# motor_controllers_connection.net
KiCad netlist of a schematic drawn in Altium Designer
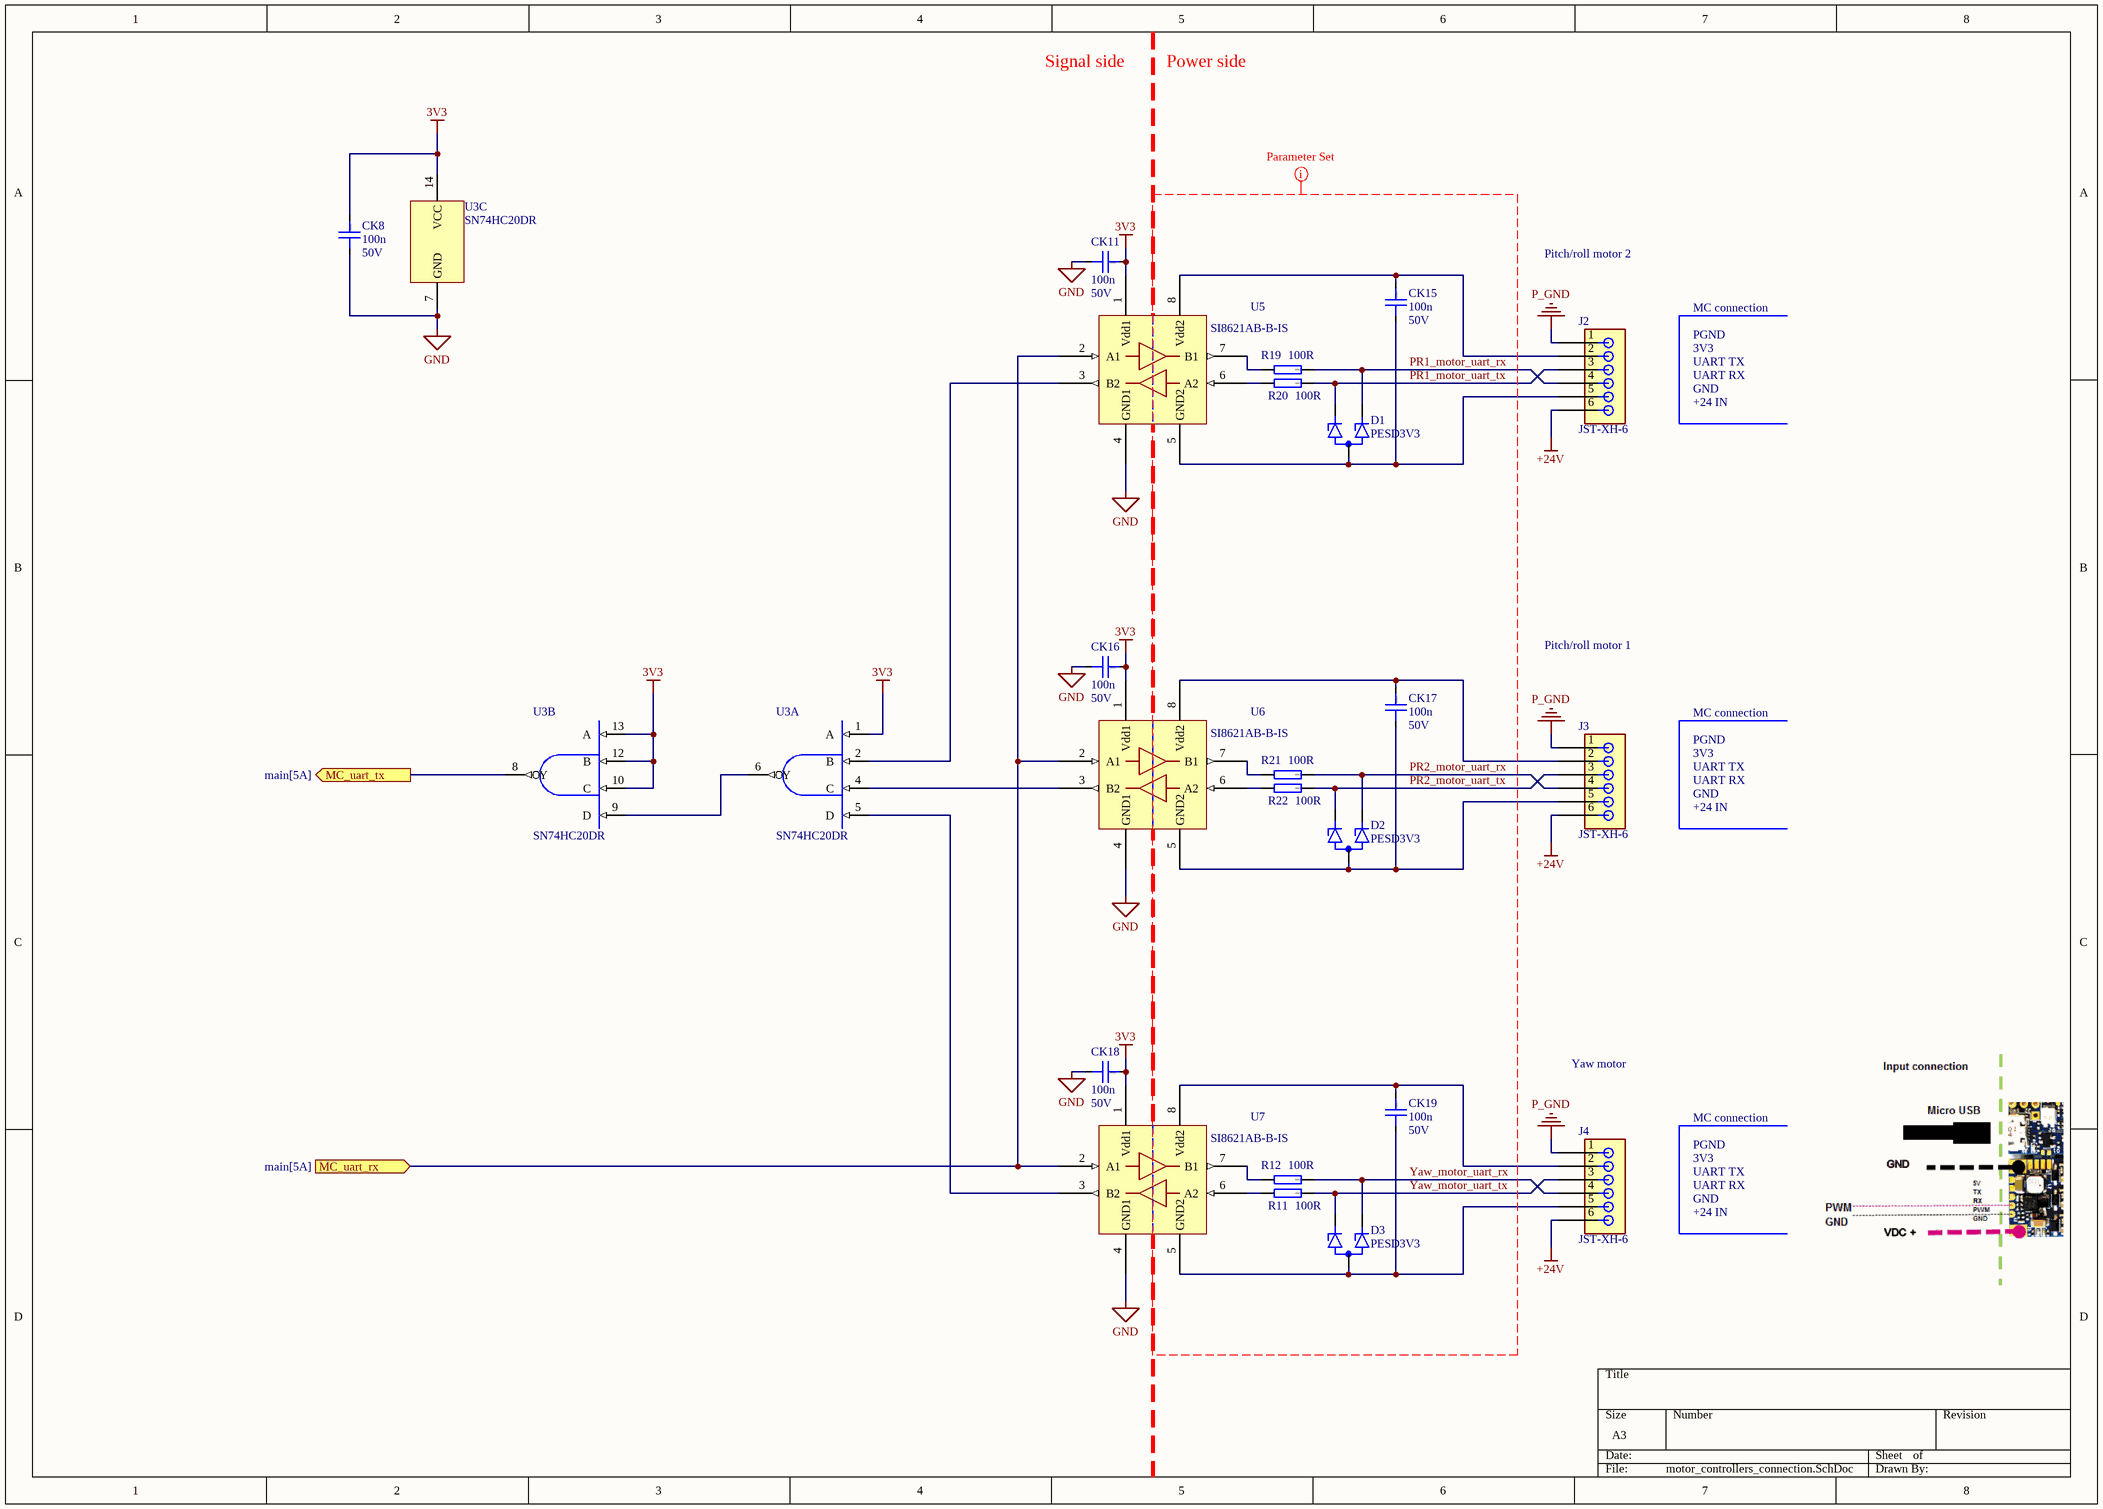
[diagram p0: motor_controllers_connection.SchDoc]

(export (version "E")
  (design (tool "Eeschema 10.0.6"))
  (components
    (comp (ref "CK8")
      (value "100n")
      (footprint "CAP0603")
      (description "50V 100nF X7R ±10% 0603 Multilayer Ceramic Capacitors MLCC - SMD/SMT ROHS")
      (fields (field (name "JLCPCB PART") "C14663") (field (name "VOLTAGE RATING") "50V"))
      (libsource (lib "Kubikova ultra knihovna") (part "Cap 100n 0603"))
    )
    (comp (ref "CK11")
      (value "100n")
      (footprint "CAP0603")
      (description "50V 100nF X7R ±10% 0603 Multilayer Ceramic Capacitors MLCC - SMD/SMT ROHS")
      (fields (field (name "JLCPCB PART") "C14663") (field (name "VOLTAGE RATING") "50V"))
      (libsource (lib "Kubikova ultra knihovna") (part "Cap 100n 0603"))
    )
    (comp (ref "CK15")
      (value "100n")
      (footprint "CAP0603")
      (description "50V 100nF X7R ±10% 0603 Multilayer Ceramic Capacitors MLCC - SMD/SMT ROHS")
      (fields (field (name "JLCPCB PART") "C14663") (field (name "VOLTAGE RATING") "50V"))
      (libsource (lib "Kubikova ultra knihovna") (part "Cap 100n 0603"))
    )
    (comp (ref "CK16")
      (value "100n")
      (footprint "CAP0603")
      (description "50V 100nF X7R ±10% 0603 Multilayer Ceramic Capacitors MLCC - SMD/SMT ROHS")
      (fields (field (name "JLCPCB PART") "C14663") (field (name "VOLTAGE RATING") "50V"))
      (libsource (lib "Kubikova ultra knihovna") (part "Cap 100n 0603"))
    )
    (comp (ref "CK17")
      (value "100n")
      (footprint "CAP0603")
      (description "50V 100nF X7R ±10% 0603 Multilayer Ceramic Capacitors MLCC - SMD/SMT ROHS")
      (fields (field (name "JLCPCB PART") "C14663") (field (name "VOLTAGE RATING") "50V"))
      (libsource (lib "Kubikova ultra knihovna") (part "Cap 100n 0603"))
    )
    (comp (ref "CK18")
      (value "100n")
      (footprint "CAP0603")
      (description "50V 100nF X7R ±10% 0603 Multilayer Ceramic Capacitors MLCC - SMD/SMT ROHS")
      (fields (field (name "JLCPCB PART") "C14663") (field (name "VOLTAGE RATING") "50V"))
      (libsource (lib "Kubikova ultra knihovna") (part "Cap 100n 0603"))
    )
    (comp (ref "CK19")
      (value "100n")
      (footprint "CAP0603")
      (description "50V 100nF X7R ±10% 0603 Multilayer Ceramic Capacitors MLCC - SMD/SMT ROHS")
      (fields (field (name "JLCPCB PART") "C14663") (field (name "VOLTAGE RATING") "50V"))
      (libsource (lib "Kubikova ultra knihovna") (part "Cap 100n 0603"))
    )
    (comp (ref "D1")
      (value "PESD3V3")
      (footprint "SOT95P230X110-3N(SOT23)")
      (description "18A 20V 5.2V Unidirectional 3.3V SOT-23 ESD and Surge Protection (TVS/ESD) ROHS")
      (fields (field (name "JLCPCB PART") "C84276") (field (name "TME PART") "PESD3V3S2UT.215"))
      (libsource (lib "Kubikova ultra knihovna") (part "PESD3V3S2UT,215"))
    )
    (comp (ref "D2")
      (value "PESD3V3")
      (footprint "SOT95P230X110-3N(SOT23)")
      (description "18A 20V 5.2V Unidirectional 3.3V SOT-23 ESD and Surge Protection (TVS/ESD) ROHS")
      (fields (field (name "JLCPCB PART") "C84276") (field (name "TME PART") "PESD3V3S2UT.215"))
      (libsource (lib "Kubikova ultra knihovna") (part "PESD3V3S2UT,215"))
    )
    (comp (ref "D3")
      (value "PESD3V3")
      (footprint "SOT95P230X110-3N(SOT23)")
      (description "18A 20V 5.2V Unidirectional 3.3V SOT-23 ESD and Surge Protection (TVS/ESD) ROHS")
      (fields (field (name "JLCPCB PART") "C84276") (field (name "TME PART") "PESD3V3S2UT.215"))
      (libsource (lib "Kubikova ultra knihovna") (part "PESD3V3S2UT,215"))
    )
    (comp (ref "J2")
      (value "JST-XH-6")
      (footprint "JST-XH-6")
      (fields (field (name "JLCPCB PART") "C157919") (field (name "TME PART") "S6B-XH-A"))
      (libsource (lib "Kubikova ultra knihovna") (part "JST-HX-6"))
    )
    (comp (ref "J3")
      (value "JST-XH-6")
      (footprint "JST-XH-6")
      (fields (field (name "JLCPCB PART") "C157919") (field (name "TME PART") "S6B-XH-A"))
      (libsource (lib "Kubikova ultra knihovna") (part "JST-HX-6"))
    )
    (comp (ref "J4")
      (value "JST-XH-6")
      (footprint "JST-XH-6")
      (fields (field (name "JLCPCB PART") "C157919") (field (name "TME PART") "S6B-XH-A"))
      (libsource (lib "Kubikova ultra knihovna") (part "JST-HX-6"))
    )
    (comp (ref "R11")
      (value "100R")
      (footprint "RESC2012X06N(SMR0805)")
      (description "125mW Thick Film Resistors 150V ±100ppm/℃ ±1% 100Ω 0805 Chip Resistor - Surface Mount ROHS")
      (fields (field (name "JLCPCB PART") "C17408") (field (name "AUTHOR") "JP/27.03.2014"))
      (libsource (lib "Kubikova ultra knihovna") (part "Res 100R 0805"))
    )
    (comp (ref "R12")
      (value "100R")
      (footprint "RESC2012X06N(SMR0805)")
      (description "125mW Thick Film Resistors 150V ±100ppm/℃ ±1% 100Ω 0805 Chip Resistor - Surface Mount ROHS")
      (fields (field (name "JLCPCB PART") "C17408") (field (name "AUTHOR") "JP/27.03.2014"))
      (libsource (lib "Kubikova ultra knihovna") (part "Res 100R 0805"))
    )
    (comp (ref "R19")
      (value "100R")
      (footprint "RESC2012X06N(SMR0805)")
      (description "125mW Thick Film Resistors 150V ±100ppm/℃ ±1% 100Ω 0805 Chip Resistor - Surface Mount ROHS")
      (fields (field (name "JLCPCB PART") "C17408") (field (name "AUTHOR") "JP/27.03.2014"))
      (libsource (lib "Kubikova ultra knihovna") (part "Res 100R 0805"))
    )
    (comp (ref "R20")
      (value "100R")
      (footprint "RESC2012X06N(SMR0805)")
      (description "125mW Thick Film Resistors 150V ±100ppm/℃ ±1% 100Ω 0805 Chip Resistor - Surface Mount ROHS")
      (fields (field (name "JLCPCB PART") "C17408") (field (name "AUTHOR") "JP/27.03.2014"))
      (libsource (lib "Kubikova ultra knihovna") (part "Res 100R 0805"))
    )
    (comp (ref "R21")
      (value "100R")
      (footprint "RESC2012X06N(SMR0805)")
      (description "125mW Thick Film Resistors 150V ±100ppm/℃ ±1% 100Ω 0805 Chip Resistor - Surface Mount ROHS")
      (fields (field (name "JLCPCB PART") "C17408") (field (name "AUTHOR") "JP/27.03.2014"))
      (libsource (lib "Kubikova ultra knihovna") (part "Res 100R 0805"))
    )
    (comp (ref "R22")
      (value "100R")
      (footprint "RESC2012X06N(SMR0805)")
      (description "125mW Thick Film Resistors 150V ±100ppm/℃ ±1% 100Ω 0805 Chip Resistor - Surface Mount ROHS")
      (fields (field (name "JLCPCB PART") "C17408") (field (name "AUTHOR") "JP/27.03.2014"))
      (libsource (lib "Kubikova ultra knihovna") (part "Res 100R 0805"))
    )
    (comp (ref "U3")
      (value "SN74HC20DR")
      (footprint "SOIC14")
      (description "2V~6V 2uA 2 19ns@6V,50pF NAND Gates SOIC-14 Logic Gates ROHS")
      (fields (field (name "JLCPCB PART") "C2867684"))
      (libsource (lib "Kubikova ultra knihovna") (part "SN74HC20DR"))
    )
    (comp (ref "U5")
      (value "SI8621AB-B-IS")
      (footprint "SOIC8")
      (description "SOIC-8 Digital Isolators ROHS")
      (fields (field (name "JLCPCB PART") "C430265"))
      (libsource (lib "Kubikova ultra knihovna") (part "SI8621AB-B-IS"))
    )
    (comp (ref "U6")
      (value "SI8621AB-B-IS")
      (footprint "SOIC8")
      (description "SOIC-8 Digital Isolators ROHS")
      (fields (field (name "JLCPCB PART") "C430265"))
      (libsource (lib "Kubikova ultra knihovna") (part "SI8621AB-B-IS"))
    )
    (comp (ref "U7")
      (value "SI8621AB-B-IS")
      (footprint "SOIC8")
      (description "SOIC-8 Digital Isolators ROHS")
      (fields (field (name "JLCPCB PART") "C430265"))
      (libsource (lib "Kubikova ultra knihovna") (part "SI8621AB-B-IS"))
    )
  )
  (nets
    (net (code "1") (name "+24V") (class "Default")
      (node (ref "J2") (pin "6") (pinfunction "6_6") (pintype "passive"))
      (node (ref "J3") (pin "6") (pinfunction "6_6") (pintype "passive"))
      (node (ref "J4") (pin "6") (pinfunction "6_6") (pintype "passive"))
    )
    (net (code "2") (name "/MC_uart_rx") (class "Default")
      (node (ref "U5") (pin "2") (pinfunction "A1_2") (pintype "input"))
      (node (ref "U6") (pin "2") (pinfunction "A1_2") (pintype "input"))
      (node (ref "U7") (pin "2") (pinfunction "A1_2") (pintype "input"))
    )
    (net (code "3") (name "/MC_uart_tx") (class "Default")
      (node (ref "U3") (pin "8") (pinfunction "Y_8") (pintype "output"))
    )
    (net (code "4") (name "/PR1_motor_uart_rx") (class "Default")
      (node (ref "D1") (pin "1") (pinfunction "K1_1") (pintype "passive"))
      (node (ref "J2") (pin "4") (pinfunction "4_4") (pintype "passive"))
      (node (ref "R19") (pin "2") (pinfunction "2_2") (pintype "passive"))
    )
    (net (code "5") (name "/PR1_motor_uart_tx") (class "Default")
      (node (ref "D1") (pin "2") (pinfunction "K2_2") (pintype "passive"))
      (node (ref "J2") (pin "3") (pinfunction "3_3") (pintype "passive"))
      (node (ref "R20") (pin "2") (pinfunction "2_2") (pintype "passive"))
    )
    (net (code "6") (name "/PR2_motor_uart_rx") (class "Default")
      (node (ref "D2") (pin "1") (pinfunction "K1_1") (pintype "passive"))
      (node (ref "J3") (pin "4") (pinfunction "4_4") (pintype "passive"))
      (node (ref "R21") (pin "2") (pinfunction "2_2") (pintype "passive"))
    )
    (net (code "7") (name "/PR2_motor_uart_tx") (class "Default")
      (node (ref "D2") (pin "2") (pinfunction "K2_2") (pintype "passive"))
      (node (ref "J3") (pin "3") (pinfunction "3_3") (pintype "passive"))
      (node (ref "R22") (pin "2") (pinfunction "2_2") (pintype "passive"))
    )
    (net (code "8") (name "/Yaw_motor_uart_rx") (class "Default")
      (node (ref "D3") (pin "1") (pinfunction "K1_1") (pintype "passive"))
      (node (ref "J4") (pin "4") (pinfunction "4_4") (pintype "passive"))
      (node (ref "R12") (pin "2") (pinfunction "2_2") (pintype "passive"))
    )
    (net (code "9") (name "/Yaw_motor_uart_tx") (class "Default")
      (node (ref "D3") (pin "2") (pinfunction "K2_2") (pintype "passive"))
      (node (ref "J4") (pin "3") (pinfunction "3_3") (pintype "passive"))
      (node (ref "R11") (pin "2") (pinfunction "2_2") (pintype "passive"))
    )
    (net (code "10") (name "3V3") (class "Default")
      (node (ref "CK11") (pin "1") (pinfunction "1_1") (pintype "passive"))
      (node (ref "CK16") (pin "1") (pinfunction "1_1") (pintype "passive"))
      (node (ref "CK18") (pin "1") (pinfunction "1_1") (pintype "passive"))
      (node (ref "CK8") (pin "1") (pinfunction "1_1") (pintype "passive"))
      (node (ref "U3") (pin "1") (pinfunction "A_1") (pintype "input"))
      (node (ref "U3") (pin "10") (pinfunction "C_10") (pintype "input"))
      (node (ref "U3") (pin "12") (pinfunction "B_12") (pintype "input"))
      (node (ref "U3") (pin "13") (pinfunction "A_13") (pintype "input"))
      (node (ref "U3") (pin "14") (pinfunction "VCC_14") (pintype "passive"))
      (node (ref "U5") (pin "1") (pinfunction "Vdd1_1") (pintype "power_in"))
      (node (ref "U6") (pin "1") (pinfunction "Vdd1_1") (pintype "power_in"))
      (node (ref "U7") (pin "1") (pinfunction "Vdd1_1") (pintype "power_in"))
    )
    (net (code "11") (name "GND") (class "Default")
      (node (ref "CK11") (pin "2") (pinfunction "2_2") (pintype "passive"))
      (node (ref "CK16") (pin "2") (pinfunction "2_2") (pintype "passive"))
      (node (ref "CK18") (pin "2") (pinfunction "2_2") (pintype "passive"))
      (node (ref "CK8") (pin "2") (pinfunction "2_2") (pintype "passive"))
      (node (ref "U3") (pin "7") (pinfunction "GND_7") (pintype "passive"))
      (node (ref "U5") (pin "4") (pinfunction "GND1_4") (pintype "power_in"))
      (node (ref "U6") (pin "4") (pinfunction "GND1_4") (pintype "power_in"))
      (node (ref "U7") (pin "4") (pinfunction "GND1_4") (pintype "power_in"))
    )
    (net (code "12") (name "Net-(D1-A)") (class "Default")
      (node (ref "CK15") (pin "2") (pinfunction "2_2") (pintype "passive"))
      (node (ref "D1") (pin "3") (pinfunction "A_3") (pintype "passive"))
      (node (ref "J2") (pin "5") (pinfunction "5_5") (pintype "passive"))
      (node (ref "U5") (pin "5") (pinfunction "GND2_5") (pintype "power_in"))
    )
    (net (code "13") (name "Net-(D2-A)") (class "Default")
      (node (ref "CK17") (pin "2") (pinfunction "2_2") (pintype "passive"))
      (node (ref "D2") (pin "3") (pinfunction "A_3") (pintype "passive"))
      (node (ref "J3") (pin "5") (pinfunction "5_5") (pintype "passive"))
      (node (ref "U6") (pin "5") (pinfunction "GND2_5") (pintype "power_in"))
    )
    (net (code "14") (name "Net-(D3-A)") (class "Default")
      (node (ref "CK19") (pin "2") (pinfunction "2_2") (pintype "passive"))
      (node (ref "D3") (pin "3") (pinfunction "A_3") (pintype "passive"))
      (node (ref "J4") (pin "5") (pinfunction "5_5") (pintype "passive"))
      (node (ref "U7") (pin "5") (pinfunction "GND2_5") (pintype "power_in"))
    )
    (net (code "15") (name "Net-(U3A-B)") (class "Default")
      (node (ref "U3") (pin "2") (pinfunction "B_2") (pintype "input"))
      (node (ref "U5") (pin "3") (pinfunction "B2_3") (pintype "output"))
    )
    (net (code "16") (name "Net-(U3A-C)") (class "Default")
      (node (ref "U3") (pin "4") (pinfunction "C_4") (pintype "input"))
      (node (ref "U6") (pin "3") (pinfunction "B2_3") (pintype "output"))
    )
    (net (code "17") (name "Net-(U3A-D)") (class "Default")
      (node (ref "U3") (pin "5") (pinfunction "D_5") (pintype "input"))
      (node (ref "U7") (pin "3") (pinfunction "B2_3") (pintype "output"))
    )
    (net (code "18") (name "Net-(U3A-Y)") (class "Default")
      (node (ref "U3") (pin "6") (pinfunction "Y_6") (pintype "output"))
      (node (ref "U3") (pin "9") (pinfunction "D_9") (pintype "input"))
    )
    (net (code "19") (name "Net-(U5-A2)") (class "Default")
      (node (ref "R20") (pin "1") (pinfunction "1_1") (pintype "passive"))
      (node (ref "U5") (pin "6") (pinfunction "A2_6") (pintype "input"))
    )
    (net (code "20") (name "Net-(U5-B1)") (class "Default")
      (node (ref "R19") (pin "1") (pinfunction "1_1") (pintype "passive"))
      (node (ref "U5") (pin "7") (pinfunction "B1_7") (pintype "output"))
    )
    (net (code "21") (name "Net-(U5-Vdd2)") (class "Default")
      (node (ref "CK15") (pin "1") (pinfunction "1_1") (pintype "passive"))
      (node (ref "J2") (pin "2") (pinfunction "2_2") (pintype "passive"))
      (node (ref "U5") (pin "8") (pinfunction "Vdd2_8") (pintype "power_in"))
    )
    (net (code "22") (name "Net-(U6-A2)") (class "Default")
      (node (ref "R22") (pin "1") (pinfunction "1_1") (pintype "passive"))
      (node (ref "U6") (pin "6") (pinfunction "A2_6") (pintype "input"))
    )
    (net (code "23") (name "Net-(U6-B1)") (class "Default")
      (node (ref "R21") (pin "1") (pinfunction "1_1") (pintype "passive"))
      (node (ref "U6") (pin "7") (pinfunction "B1_7") (pintype "output"))
    )
    (net (code "24") (name "Net-(U6-Vdd2)") (class "Default")
      (node (ref "CK17") (pin "1") (pinfunction "1_1") (pintype "passive"))
      (node (ref "J3") (pin "2") (pinfunction "2_2") (pintype "passive"))
      (node (ref "U6") (pin "8") (pinfunction "Vdd2_8") (pintype "power_in"))
    )
    (net (code "25") (name "Net-(U7-A2)") (class "Default")
      (node (ref "R11") (pin "1") (pinfunction "1_1") (pintype "passive"))
      (node (ref "U7") (pin "6") (pinfunction "A2_6") (pintype "input"))
    )
    (net (code "26") (name "Net-(U7-B1)") (class "Default")
      (node (ref "R12") (pin "1") (pinfunction "1_1") (pintype "passive"))
      (node (ref "U7") (pin "7") (pinfunction "B1_7") (pintype "output"))
    )
    (net (code "27") (name "Net-(U7-Vdd2)") (class "Default")
      (node (ref "CK19") (pin "1") (pinfunction "1_1") (pintype "passive"))
      (node (ref "J4") (pin "2") (pinfunction "2_2") (pintype "passive"))
      (node (ref "U7") (pin "8") (pinfunction "Vdd2_8") (pintype "power_in"))
    )
    (net (code "28") (name "P_GND") (class "Default")
      (node (ref "J2") (pin "1") (pinfunction "1_1") (pintype "passive"))
      (node (ref "J3") (pin "1") (pinfunction "1_1") (pintype "passive"))
      (node (ref "J4") (pin "1") (pinfunction "1_1") (pintype "passive"))
    )
  )
)
